# Sheet1.net
KiCad netlist of a schematic drawn in Altium Designer
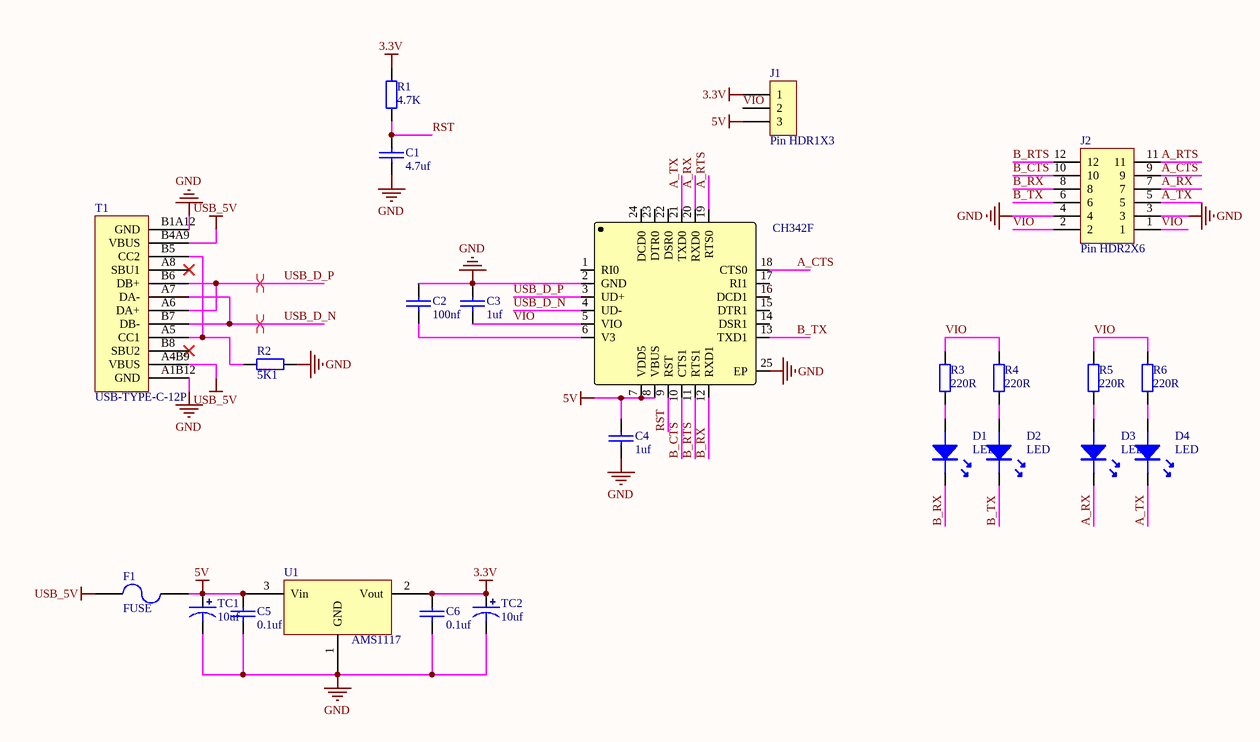
[diagram p0: Sheet1.SchDoc]

(export (version "E")
  (design (tool "Eeschema 10.0.6"))
  (components
    (comp (ref "*") (value "CH342F") (footprint "QFN24-PAD 4X4") (libsource (lib "通讯系列IC") (part "CH342F")))
    (comp (ref "C1")
      (value "4.7uf")
      (footprint "0603C")
      (description "无极性电容")
      (libsource (lib "电容") (part "CAP"))
    )
    (comp (ref "C2")
      (value "100nf")
      (footprint "0603C")
      (description "无极性电容")
      (libsource (lib "电容") (part "CAP"))
    )
    (comp (ref "C3")
      (value "1uf")
      (footprint "0603C")
      (description "无极性电容")
      (libsource (lib "电容") (part "CAP"))
    )
    (comp (ref "C4")
      (value "1uf")
      (footprint "0603C")
      (description "无极性电容")
      (libsource (lib "电容") (part "CAP"))
    )
    (comp (ref "C5")
      (value "0.1uf")
      (footprint "0603C")
      (description "无极性电容")
      (libsource (lib "电容") (part "CAP"))
    )
    (comp (ref "C6")
      (value "0.1uf")
      (footprint "0603C")
      (description "无极性电容")
      (libsource (lib "电容") (part "CAP"))
    )
    (comp (ref "D1") (value "LED") (footprint "LED-0603B") (libsource (lib "LED") (part "LED")))
    (comp (ref "D2") (value "LED") (footprint "LED-0603B") (libsource (lib "LED") (part "LED")))
    (comp (ref "D3") (value "LED") (footprint "LED-0603B") (libsource (lib "LED") (part "LED")))
    (comp (ref "D4") (value "LED") (footprint "LED-0603B") (libsource (lib "LED") (part "LED")))
    (comp (ref "F1") (value "FUSE") (footprint "FUSE-1210") (libsource (lib "保险丝") (part "FUSE")))
    (comp (ref "J1")
      (value "Pin HDR1X3")
      (footprint "Pin HDR1X3/2.54mm-S")
      (libsource (lib "排针") (part "Pin HDR1X3"))
    )
    (comp (ref "J2")
      (value "Pin HDR2X6")
      (footprint "Pin HDR2X6/2.54mm-W")
      (libsource (lib "排针") (part "Pin HDR2X6"))
    )
    (comp (ref "R1")
      (value "4.7K")
      (footprint "0603R")
      (description "贴片电阻")
      (libsource (lib "") (part "RES_1"))
    )
    (comp (ref "R2")
      (value "5K1")
      (footprint "0603R")
      (description "贴片电阻")
      (libsource (lib "Miscellaneous Base") (part "RES"))
    )
    (comp (ref "R3")
      (value "220R")
      (footprint "0603R")
      (description "贴片电阻")
      (libsource (lib "") (part "RES_1"))
    )
    (comp (ref "R4")
      (value "220R")
      (footprint "0603R")
      (description "贴片电阻")
      (libsource (lib "") (part "RES_1"))
    )
    (comp (ref "R5")
      (value "220R")
      (footprint "0603R")
      (description "贴片电阻")
      (libsource (lib "") (part "RES_1"))
    )
    (comp (ref "R6")
      (value "220R")
      (footprint "0603R")
      (description "贴片电阻")
      (libsource (lib "") (part "RES_1"))
    )
    (comp (ref "T1")
      (value "USB-TYPE-C-12P")
      (footprint "type-c-12p")
      (libsource (lib "USB") (part "USB-TYPE-C-12P"))
    )
    (comp (ref "TC1")
      (value "10uf")
      (footprint "TAJ-A/3216")
      (description "钽电容")
      (libsource (lib "电容") (part "TCAP"))
    )
    (comp (ref "TC2")
      (value "10uf")
      (footprint "TAJ-A/3216")
      (description "钽电容")
      (libsource (lib "电容") (part "TCAP"))
    )
    (comp (ref "U1")
      (value "AMS1117")
      (footprint "SOT223")
      (description "三端稳压芯片")
      (libsource (lib "电源芯片") (part "AMS1117"))
    )
  )
  (nets
    (net (code "1") (name "/A_CTS") (class "Default")
      (node (ref "*") (pin "18") (pinfunction "CTS0_18") (pintype "passive"))
      (node (ref "J2") (pin "9") (pinfunction "9_9") (pintype "passive"))
    )
    (net (code "2") (name "/A_RTS") (class "Default")
      (node (ref "*") (pin "19") (pinfunction "RTS0_19") (pintype "passive"))
      (node (ref "J2") (pin "11") (pinfunction "11_11") (pintype "passive"))
    )
    (net (code "3") (name "/A_RX") (class "Default")
      (node (ref "*") (pin "20") (pinfunction "RXD0_20") (pintype "passive"))
      (node (ref "D3") (pin "K") (pinfunction "K_K") (pintype "passive"))
      (node (ref "J2") (pin "7") (pinfunction "7_7") (pintype "passive"))
    )
    (net (code "4") (name "/A_TX") (class "Default")
      (node (ref "*") (pin "21") (pinfunction "TXD0_21") (pintype "passive"))
      (node (ref "D4") (pin "K") (pinfunction "K_K") (pintype "passive"))
      (node (ref "J2") (pin "5") (pinfunction "5_5") (pintype "passive"))
    )
    (net (code "5") (name "/B_CTS") (class "Default")
      (node (ref "*") (pin "10") (pinfunction "CTS1_10") (pintype "passive"))
      (node (ref "J2") (pin "10") (pinfunction "10_10") (pintype "passive"))
    )
    (net (code "6") (name "/B_RTS") (class "Default")
      (node (ref "*") (pin "11") (pinfunction "RTS1_11") (pintype "passive"))
      (node (ref "J2") (pin "12") (pinfunction "12_12") (pintype "passive"))
    )
    (net (code "7") (name "/B_RX") (class "Default")
      (node (ref "*") (pin "12") (pinfunction "RXD1_12") (pintype "passive"))
      (node (ref "D1") (pin "K") (pinfunction "K_K") (pintype "passive"))
      (node (ref "J2") (pin "8") (pinfunction "8_8") (pintype "passive"))
    )
    (net (code "8") (name "/B_TX") (class "Default")
      (node (ref "*") (pin "13") (pinfunction "TXD1_13") (pintype "passive"))
      (node (ref "D2") (pin "K") (pinfunction "K_K") (pintype "passive"))
      (node (ref "J2") (pin "6") (pinfunction "6_6") (pintype "passive"))
    )
    (net (code "9") (name "/RST") (class "Default")
      (node (ref "*") (pin "9") (pinfunction "RST_9") (pintype "passive"))
      (node (ref "C1") (pin "1") (pinfunction "1_1") (pintype "passive"))
      (node (ref "R1") (pin "2") (pinfunction "2_2") (pintype "passive"))
    )
    (net (code "10") (name "/USB_D_N") (class "Default")
      (node (ref "*") (pin "4") (pinfunction "UD-_4") (pintype "passive"))
      (node (ref "T1") (pin "A7") (pinfunction "DA-_A7") (pintype "passive"))
      (node (ref "T1") (pin "B7") (pinfunction "DB-_B7") (pintype "passive"))
    )
    (net (code "11") (name "/USB_D_P") (class "Default")
      (node (ref "*") (pin "3") (pinfunction "UD+_3") (pintype "passive"))
      (node (ref "T1") (pin "A6") (pinfunction "DA+_A6") (pintype "passive"))
      (node (ref "T1") (pin "B6") (pinfunction "DB+_B6") (pintype "passive"))
    )
    (net (code "12") (name "/VIO") (class "Default")
      (node (ref "*") (pin "5") (pinfunction "VIO_5") (pintype "passive"))
      (node (ref "C3") (pin "2") (pinfunction "2_2") (pintype "passive"))
      (node (ref "J1") (pin "2") (pinfunction "2_2") (pintype "passive"))
      (node (ref "J2") (pin "1") (pinfunction "1_1") (pintype "passive"))
      (node (ref "J2") (pin "2") (pinfunction "2_2") (pintype "passive"))
      (node (ref "R3") (pin "1") (pinfunction "1_1") (pintype "passive"))
      (node (ref "R4") (pin "1") (pinfunction "1_1") (pintype "passive"))
      (node (ref "R5") (pin "1") (pinfunction "1_1") (pintype "passive"))
      (node (ref "R6") (pin "1") (pinfunction "1_1") (pintype "passive"))
    )
    (net (code "13") (name "3.3V") (class "Default")
      (node (ref "C6") (pin "2") (pinfunction "2_2") (pintype "passive"))
      (node (ref "J1") (pin "1") (pinfunction "1_1") (pintype "passive"))
      (node (ref "R1") (pin "1") (pinfunction "1_1") (pintype "passive"))
      (node (ref "TC2") (pin "1") (pinfunction "1_1") (pintype "passive"))
      (node (ref "U1") (pin "2") (pinfunction "Vout_2") (pintype "passive"))
    )
    (net (code "14") (name "5V") (class "Default")
      (node (ref "*") (pin "7") (pinfunction "VDD5_7") (pintype "passive"))
      (node (ref "*") (pin "8") (pinfunction "VBUS_8") (pintype "passive"))
      (node (ref "C4") (pin "2") (pinfunction "2_2") (pintype "passive"))
      (node (ref "C5") (pin "2") (pinfunction "2_2") (pintype "passive"))
      (node (ref "F1") (pin "2") (pinfunction "2_2") (pintype "passive"))
      (node (ref "J1") (pin "3") (pinfunction "3_3") (pintype "passive"))
      (node (ref "TC1") (pin "1") (pinfunction "1_1") (pintype "passive"))
      (node (ref "U1") (pin "3") (pinfunction "Vin_3") (pintype "passive"))
    )
    (net (code "15") (name "GND") (class "Default")
      (node (ref "*") (pin "2") (pinfunction "GND_2") (pintype "passive"))
      (node (ref "*") (pin "25") (pinfunction "EP_25") (pintype "passive"))
      (node (ref "C1") (pin "2") (pinfunction "2_2") (pintype "passive"))
      (node (ref "C2") (pin "1") (pinfunction "1_1") (pintype "passive"))
      (node (ref "C3") (pin "1") (pinfunction "1_1") (pintype "passive"))
      (node (ref "C4") (pin "1") (pinfunction "1_1") (pintype "passive"))
      (node (ref "C5") (pin "1") (pinfunction "1_1") (pintype "passive"))
      (node (ref "C6") (pin "1") (pinfunction "1_1") (pintype "passive"))
      (node (ref "J2") (pin "3") (pinfunction "3_3") (pintype "passive"))
      (node (ref "J2") (pin "4") (pinfunction "4_4") (pintype "passive"))
      (node (ref "R2") (pin "1") (pinfunction "1_1") (pintype "passive"))
      (node (ref "T1") (pin "A1B12") (pinfunction "GND_A1B12") (pintype "passive"))
      (node (ref "T1") (pin "B1A12") (pinfunction "GND_B1A12") (pintype "passive"))
      (node (ref "TC1") (pin "2") (pinfunction "2_2") (pintype "passive"))
      (node (ref "TC2") (pin "2") (pinfunction "2_2") (pintype "passive"))
      (node (ref "U1") (pin "1") (pinfunction "GND_1") (pintype "passive"))
    )
    (net (code "16") (name "Net-(*-V3)") (class "Default")
      (node (ref "*") (pin "6") (pinfunction "V3_6") (pintype "passive"))
      (node (ref "C2") (pin "2") (pinfunction "2_2") (pintype "passive"))
    )
    (net (code "17") (name "Net-(D1-PadA)") (class "Default")
      (node (ref "D1") (pin "A") (pinfunction "A_A") (pintype "passive"))
      (node (ref "R3") (pin "2") (pinfunction "2_2") (pintype "passive"))
    )
    (net (code "18") (name "Net-(D2-PadA)") (class "Default")
      (node (ref "D2") (pin "A") (pinfunction "A_A") (pintype "passive"))
      (node (ref "R4") (pin "2") (pinfunction "2_2") (pintype "passive"))
    )
    (net (code "19") (name "Net-(D3-PadA)") (class "Default")
      (node (ref "D3") (pin "A") (pinfunction "A_A") (pintype "passive"))
      (node (ref "R5") (pin "2") (pinfunction "2_2") (pintype "passive"))
    )
    (net (code "20") (name "Net-(D4-PadA)") (class "Default")
      (node (ref "D4") (pin "A") (pinfunction "A_A") (pintype "passive"))
      (node (ref "R6") (pin "2") (pinfunction "2_2") (pintype "passive"))
    )
    (net (code "21") (name "Net-(T1-CC1)") (class "Default")
      (node (ref "R2") (pin "2") (pinfunction "2_2") (pintype "passive"))
      (node (ref "T1") (pin "A5") (pinfunction "CC1_A5") (pintype "passive"))
      (node (ref "T1") (pin "B5") (pinfunction "CC2_B5") (pintype "passive"))
    )
    (net (code "22") (name "USB_5V") (class "Default")
      (node (ref "F1") (pin "1") (pinfunction "1_1") (pintype "passive"))
      (node (ref "T1") (pin "A4B9") (pinfunction "VBUS_A4B9") (pintype "passive"))
      (node (ref "T1") (pin "B4A9") (pinfunction "VBUS_B4A9") (pintype "passive"))
    )
    (net (code "23") (name "unconnected-(*-DCD0-Pad24)") (class "Default")
      (node (ref "*") (pin "24") (pinfunction "DCD0_24") (pintype "passive"))
    )
    (net (code "24") (name "unconnected-(*-DCD1-Pad16)") (class "Default")
      (node (ref "*") (pin "16") (pinfunction "DCD1_16") (pintype "passive"))
    )
    (net (code "25") (name "unconnected-(*-DSR0-Pad22)") (class "Default")
      (node (ref "*") (pin "22") (pinfunction "DSR0_22") (pintype "passive"))
    )
    (net (code "26") (name "unconnected-(*-DSR1-Pad14)") (class "Default")
      (node (ref "*") (pin "14") (pinfunction "DSR1_14") (pintype "passive"))
    )
    (net (code "27") (name "unconnected-(*-DTR0-Pad23)") (class "Default")
      (node (ref "*") (pin "23") (pinfunction "DTR0_23") (pintype "passive"))
    )
    (net (code "28") (name "unconnected-(*-DTR1-Pad15)") (class "Default")
      (node (ref "*") (pin "15") (pinfunction "DTR1_15") (pintype "passive"))
    )
    (net (code "29") (name "unconnected-(*-RI0-Pad1)") (class "Default")
      (node (ref "*") (pin "1") (pinfunction "RI0_1") (pintype "passive"))
    )
    (net (code "30") (name "unconnected-(*-RI1-Pad17)") (class "Default")
      (node (ref "*") (pin "17") (pinfunction "RI1_17") (pintype "passive"))
    )
    (net (code "31") (name "unconnected-(T1-SBU1-PadA8)") (class "Default")
      (node (ref "T1") (pin "A8") (pinfunction "SBU1_A8") (pintype "passive+no_connect"))
    )
    (net (code "32") (name "unconnected-(T1-SBU2-PadB8)") (class "Default")
      (node (ref "T1") (pin "B8") (pinfunction "SBU2_B8") (pintype "passive+no_connect"))
    )
  )
)
